# YakupTrkn1.net
KiCad netlist of a schematic drawn in Altium Designer
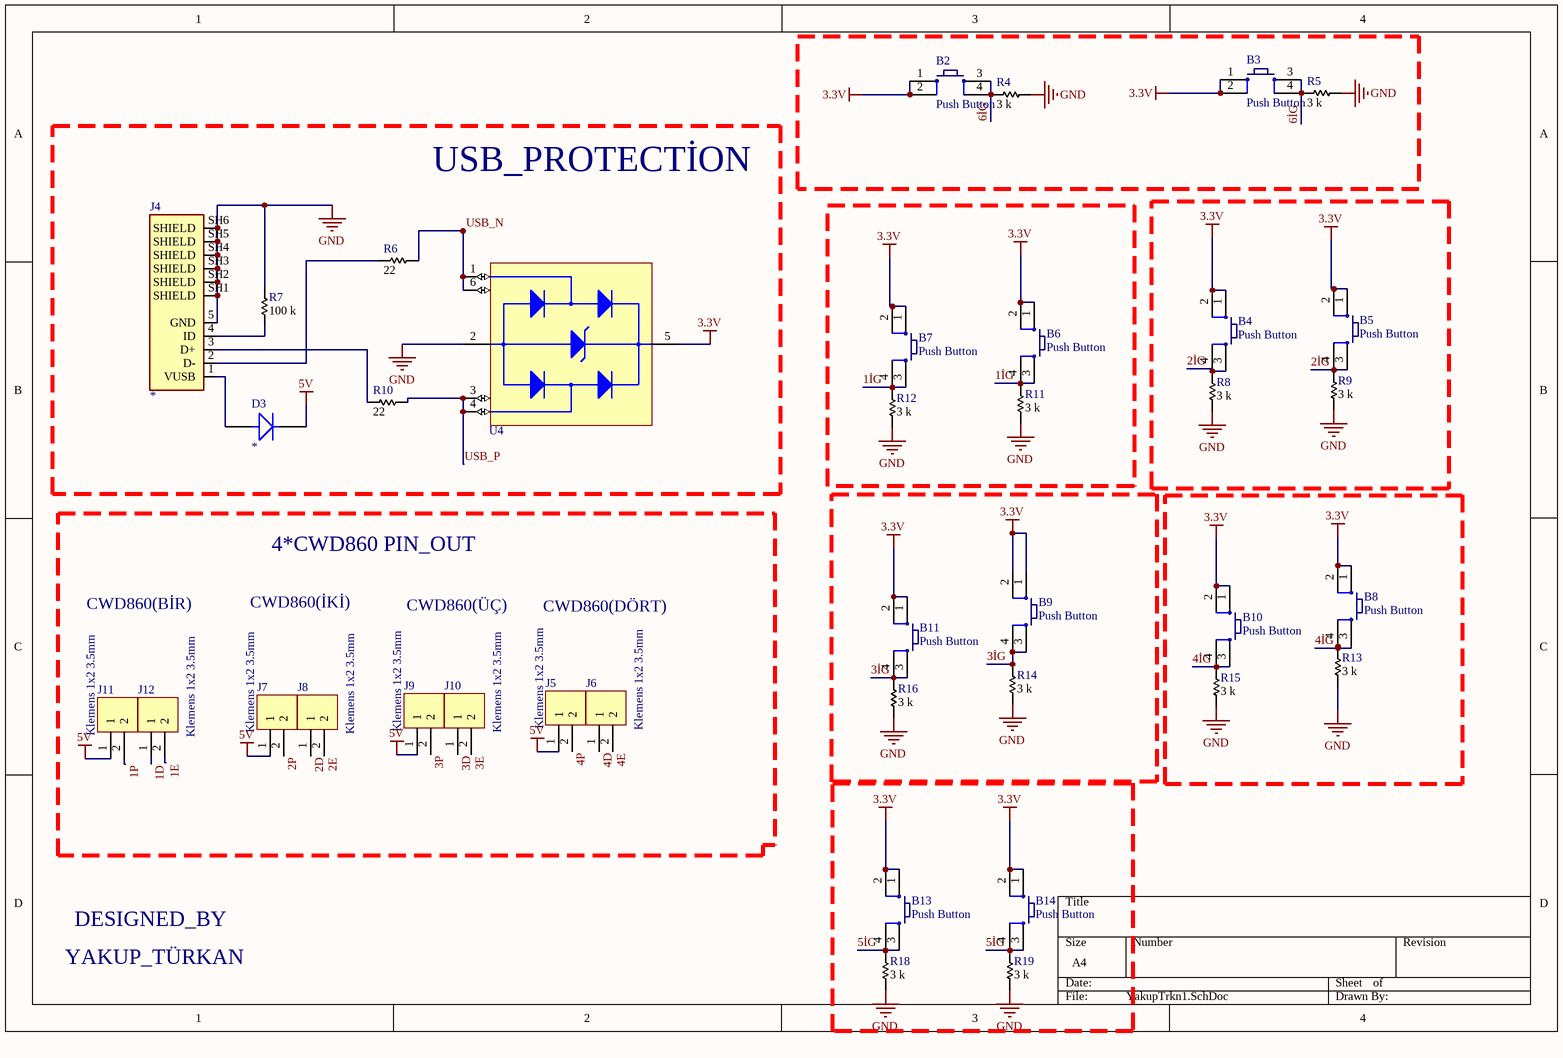
[diagram p0: YakupTrkn1.SchDoc]

(export (version "E")
  (design (tool "Eeschema 10.0.6"))
  (components
    (comp (ref "B2")
      (value "Push Button")
      (footprint "PUSB BUTTON-SMD")
      (description "Smd Push Button")
      (libsource (lib "YakupTrkn") (part "Push Button"))
    )
    (comp (ref "B3")
      (value "Push Button")
      (footprint "PUSB BUTTON-SMD")
      (description "Smd Push Button")
      (libsource (lib "YakupTrkn") (part "Push Button"))
    )
    (comp (ref "B4")
      (value "Push Button")
      (footprint "PUSB BUTTON-SMD")
      (description "Smd Push Button")
      (libsource (lib "YakupTrkn") (part "Push Button"))
    )
    (comp (ref "B5")
      (value "Push Button")
      (footprint "PUSB BUTTON-SMD")
      (description "Smd Push Button")
      (libsource (lib "YakupTrkn") (part "Push Button"))
    )
    (comp (ref "B6")
      (value "Push Button")
      (footprint "PUSB BUTTON-SMD")
      (description "Smd Push Button")
      (libsource (lib "YakupTrkn") (part "Push Button"))
    )
    (comp (ref "B7")
      (value "Push Button")
      (footprint "PUSB BUTTON-SMD")
      (description "Smd Push Button")
      (libsource (lib "YakupTrkn") (part "Push Button"))
    )
    (comp (ref "B8")
      (value "Push Button")
      (footprint "PUSB BUTTON-SMD")
      (description "Smd Push Button")
      (libsource (lib "YakupTrkn") (part "Push Button"))
    )
    (comp (ref "B9")
      (value "Push Button")
      (footprint "PUSB BUTTON-SMD")
      (description "Smd Push Button")
      (libsource (lib "YakupTrkn") (part "Push Button"))
    )
    (comp (ref "B10")
      (value "Push Button")
      (footprint "PUSB BUTTON-SMD")
      (description "Smd Push Button")
      (libsource (lib "YakupTrkn") (part "Push Button"))
    )
    (comp (ref "B11")
      (value "Push Button")
      (footprint "PUSB BUTTON-SMD")
      (description "Smd Push Button")
      (libsource (lib "YakupTrkn") (part "Push Button"))
    )
    (comp (ref "B13")
      (value "Push Button")
      (footprint "PUSB BUTTON-SMD")
      (description "Smd Push Button")
      (libsource (lib "YakupTrkn") (part "Push Button"))
    )
    (comp (ref "B14")
      (value "Push Button")
      (footprint "PUSB BUTTON-SMD")
      (description "Smd Push Button")
      (libsource (lib "YakupTrkn") (part "Push Button"))
    )
    (comp (ref "D3")
      (value "*")
      (footprint "MBRA210LT3G:DIOM5226X220N")
      (description "...employing the Schottky Barrier principle in a metal to silicon power rectifier.")
      (fields (field (name "MF") "{'manufacturer': u'ON Semiconductor'}") (field (name "MP") "MBRA210LT3G"))
      (libsource (lib "*") (part "MBRA210LT3G"))
    )
    (comp (ref "J4")
      (value "*")
      (footprint "10118192-0001LF:AMPHENOL_10118192-0001LF")
      (description "Single Port 5 Contact Horizontal Right Angle Shielded Micro B USB 2.0 Connector")
      (fields (field (name "MP") "10118192-0001LF") (field (name "MF") "{'manufacturer': u'FCI'}"))
      (libsource (lib "*") (part "10118192-0001LF"))
    )
    (comp (ref "J5")
      (value "Klemens 1x2 3.5mm")
      (footprint "Klemens 1x2 - 3.5mm")
      (libsource (lib "YakupTrkn") (part "Klemens 1x2 3.5mm"))
    )
    (comp (ref "J6")
      (value "Klemens 1x2 3.5mm")
      (footprint "Klemens 1x2 - 3.5mm")
      (libsource (lib "YakupTrkn") (part "Klemens 1x2 3.5mm"))
    )
    (comp (ref "J7")
      (value "Klemens 1x2 3.5mm")
      (footprint "Klemens 1x2 - 3.5mm")
      (libsource (lib "YakupTrkn") (part "Klemens 1x2 3.5mm"))
    )
    (comp (ref "J8")
      (value "Klemens 1x2 3.5mm")
      (footprint "Klemens 1x2 - 3.5mm")
      (libsource (lib "YakupTrkn") (part "Klemens 1x2 3.5mm"))
    )
    (comp (ref "J9")
      (value "Klemens 1x2 3.5mm")
      (footprint "Klemens 1x2 - 3.5mm")
      (libsource (lib "YakupTrkn") (part "Klemens 1x2 3.5mm"))
    )
    (comp (ref "J10")
      (value "Klemens 1x2 3.5mm")
      (footprint "Klemens 1x2 - 3.5mm")
      (libsource (lib "YakupTrkn") (part "Klemens 1x2 3.5mm"))
    )
    (comp (ref "J11")
      (value "Klemens 1x2 3.5mm")
      (footprint "Klemens 1x2 - 3.5mm")
      (libsource (lib "YakupTrkn") (part "Klemens 1x2 3.5mm"))
    )
    (comp (ref "J12")
      (value "Klemens 1x2 3.5mm")
      (footprint "Klemens 1x2 - 3.5mm")
      (libsource (lib "YakupTrkn") (part "Klemens 1x2 3.5mm"))
    )
    (comp (ref "R4")
      (value "0805S8F3001T5E")
      (footprint "ROYALOHM_RES_0805")
      (description "RES SMD 3K OHM 1% 1/8W 0805")
      (fields (field (name "RESISTANCE") "3 k"))
      (libsource (lib "YakupTrkn") (part "0805S8F3001T5E"))
    )
    (comp (ref "R5")
      (value "0805S8F3001T5E")
      (footprint "ROYALOHM_RES_0805")
      (description "RES SMD 3K OHM 1% 1/8W 0805")
      (fields (field (name "RESISTANCE") "3 k"))
      (libsource (lib "YakupTrkn") (part "0805S8F3001T5E"))
    )
    (comp (ref "R6")
      (value "0805W8J0220T5E")
      (footprint "ROYALOHM_RES_0805")
      (description "RES SMD 22 OHM 5% 1/8W 0805")
      (fields (field (name "RESISTANCE") "22"))
      (libsource (lib "YakupTrkn") (part "0805W8J0220T5E"))
    )
    (comp (ref "R7")
      (value "0603SAJ0104T5E")
      (footprint "ROYALOHM_RES_0603")
      (description "RES SMD 100K OHM 5% 1/10W 0603")
      (fields (field (name "RESISTANCE") "100 k"))
      (libsource (lib "YakupTrkn") (part "0603SAJ0104T5E"))
    )
    (comp (ref "R8")
      (value "0805S8F3001T5E")
      (footprint "ROYALOHM_RES_0805")
      (description "RES SMD 3K OHM 1% 1/8W 0805")
      (fields (field (name "RESISTANCE") "3 k"))
      (libsource (lib "YakupTrkn") (part "0805S8F3001T5E"))
    )
    (comp (ref "R9")
      (value "0805S8F3001T5E")
      (footprint "ROYALOHM_RES_0805")
      (description "RES SMD 3K OHM 1% 1/8W 0805")
      (fields (field (name "RESISTANCE") "3 k"))
      (libsource (lib "YakupTrkn") (part "0805S8F3001T5E"))
    )
    (comp (ref "R10")
      (value "0805W8J0220T5E")
      (footprint "ROYALOHM_RES_0805")
      (description "RES SMD 22 OHM 5% 1/8W 0805")
      (fields (field (name "RESISTANCE") "22"))
      (libsource (lib "YakupTrkn") (part "0805W8J0220T5E"))
    )
    (comp (ref "R11")
      (value "0805S8F3001T5E")
      (footprint "ROYALOHM_RES_0805")
      (description "RES SMD 3K OHM 1% 1/8W 0805")
      (fields (field (name "RESISTANCE") "3 k"))
      (libsource (lib "YakupTrkn") (part "0805S8F3001T5E"))
    )
    (comp (ref "R12")
      (value "0805S8F3001T5E")
      (footprint "ROYALOHM_RES_0805")
      (description "RES SMD 3K OHM 1% 1/8W 0805")
      (fields (field (name "RESISTANCE") "3 k"))
      (libsource (lib "YakupTrkn") (part "0805S8F3001T5E"))
    )
    (comp (ref "R13")
      (value "0805S8F3001T5E")
      (footprint "ROYALOHM_RES_0805")
      (description "RES SMD 3K OHM 1% 1/8W 0805")
      (fields (field (name "RESISTANCE") "3 k"))
      (libsource (lib "YakupTrkn") (part "0805S8F3001T5E"))
    )
    (comp (ref "R14")
      (value "0805S8F3001T5E")
      (footprint "ROYALOHM_RES_0805")
      (description "RES SMD 3K OHM 1% 1/8W 0805")
      (fields (field (name "RESISTANCE") "3 k"))
      (libsource (lib "YakupTrkn") (part "0805S8F3001T5E"))
    )
    (comp (ref "R15")
      (value "0805S8F3001T5E")
      (footprint "ROYALOHM_RES_0805")
      (description "RES SMD 3K OHM 1% 1/8W 0805")
      (fields (field (name "RESISTANCE") "3 k"))
      (libsource (lib "YakupTrkn") (part "0805S8F3001T5E"))
    )
    (comp (ref "R16")
      (value "0805S8F3001T5E")
      (footprint "ROYALOHM_RES_0805")
      (description "RES SMD 3K OHM 1% 1/8W 0805")
      (fields (field (name "RESISTANCE") "3 k"))
      (libsource (lib "YakupTrkn") (part "0805S8F3001T5E"))
    )
    (comp (ref "R18")
      (value "0805S8F3001T5E")
      (footprint "ROYALOHM_RES_0805")
      (description "RES SMD 3K OHM 1% 1/8W 0805")
      (fields (field (name "RESISTANCE") "3 k"))
      (libsource (lib "YakupTrkn") (part "0805S8F3001T5E"))
    )
    (comp (ref "R19")
      (value "0805S8F3001T5E")
      (footprint "ROYALOHM_RES_0805")
      (description "RES SMD 3K OHM 1% 1/8W 0805")
      (fields (field (name "RESISTANCE") "3 k"))
      (libsource (lib "YakupTrkn") (part "0805S8F3001T5E"))
    )
    (comp (ref "U4")
      (value "USBLC6-2SC6")
      (footprint "SOT23-6L")
      (description "TVS DIODE 5.25V 17V SOT23-6")
      (fields (field (name "MANUFACTURER") "STMicroelectronics") (field (name "DESIGNED BY") "BERK"))
      (libsource (lib "YakupTrkn") (part "USB PROTECTION"))
    )
  )
  (nets
    (net (code "1") (name "/1D") (class "Default")
      (node (ref "J12") (pin "1") (pinfunction "1_1") (pintype "passive"))
    )
    (net (code "2") (name "/1E") (class "Default")
      (node (ref "J12") (pin "2") (pinfunction "2_2") (pintype "passive"))
    )
    (net (code "3") (name "/1P") (class "Default")
      (node (ref "J11") (pin "2") (pinfunction "2_2") (pintype "passive"))
    )
    (net (code "4") (name "/1İG") (class "Default")
      (node (ref "B6") (pin "3") (pinfunction "3_3") (pintype "passive"))
      (node (ref "B6") (pin "4") (pinfunction "4_4") (pintype "passive"))
      (node (ref "B7") (pin "3") (pinfunction "3_3") (pintype "passive"))
      (node (ref "B7") (pin "4") (pinfunction "4_4") (pintype "passive"))
      (node (ref "R11") (pin "2") (pinfunction "2_2") (pintype "passive"))
      (node (ref "R12") (pin "2") (pinfunction "2_2") (pintype "passive"))
    )
    (net (code "5") (name "/2D") (class "Default")
      (node (ref "J8") (pin "1") (pinfunction "1_1") (pintype "passive"))
    )
    (net (code "6") (name "/2E") (class "Default")
      (node (ref "J8") (pin "2") (pinfunction "2_2") (pintype "passive"))
    )
    (net (code "7") (name "/2P") (class "Default")
      (node (ref "J7") (pin "2") (pinfunction "2_2") (pintype "passive"))
    )
    (net (code "8") (name "/2İG") (class "Default")
      (node (ref "B4") (pin "3") (pinfunction "3_3") (pintype "passive"))
      (node (ref "B4") (pin "4") (pinfunction "4_4") (pintype "passive"))
      (node (ref "B5") (pin "3") (pinfunction "3_3") (pintype "passive"))
      (node (ref "B5") (pin "4") (pinfunction "4_4") (pintype "passive"))
      (node (ref "R8") (pin "2") (pinfunction "2_2") (pintype "passive"))
      (node (ref "R9") (pin "2") (pinfunction "2_2") (pintype "passive"))
    )
    (net (code "9") (name "/3D") (class "Default")
      (node (ref "J10") (pin "1") (pinfunction "1_1") (pintype "passive"))
    )
    (net (code "10") (name "/3E") (class "Default")
      (node (ref "J10") (pin "2") (pinfunction "2_2") (pintype "passive"))
    )
    (net (code "11") (name "/3P") (class "Default")
      (node (ref "J9") (pin "2") (pinfunction "2_2") (pintype "passive"))
    )
    (net (code "12") (name "/3İG") (class "Default")
      (node (ref "B11") (pin "3") (pinfunction "3_3") (pintype "passive"))
      (node (ref "B11") (pin "4") (pinfunction "4_4") (pintype "passive"))
      (node (ref "B9") (pin "3") (pinfunction "3_3") (pintype "passive"))
      (node (ref "B9") (pin "4") (pinfunction "4_4") (pintype "passive"))
      (node (ref "R14") (pin "2") (pinfunction "2_2") (pintype "passive"))
      (node (ref "R16") (pin "2") (pinfunction "2_2") (pintype "passive"))
    )
    (net (code "13") (name "/4D") (class "Default")
      (node (ref "J6") (pin "1") (pinfunction "1_1") (pintype "passive"))
    )
    (net (code "14") (name "/4E") (class "Default")
      (node (ref "J6") (pin "2") (pinfunction "2_2") (pintype "passive"))
    )
    (net (code "15") (name "/4P") (class "Default")
      (node (ref "J5") (pin "2") (pinfunction "2_2") (pintype "passive"))
    )
    (net (code "16") (name "/4İG") (class "Default")
      (node (ref "B10") (pin "3") (pinfunction "3_3") (pintype "passive"))
      (node (ref "B10") (pin "4") (pinfunction "4_4") (pintype "passive"))
      (node (ref "B8") (pin "3") (pinfunction "3_3") (pintype "passive"))
      (node (ref "B8") (pin "4") (pinfunction "4_4") (pintype "passive"))
      (node (ref "R13") (pin "2") (pinfunction "2_2") (pintype "passive"))
      (node (ref "R15") (pin "2") (pinfunction "2_2") (pintype "passive"))
    )
    (net (code "17") (name "/5İG") (class "Default")
      (node (ref "B13") (pin "3") (pinfunction "3_3") (pintype "passive"))
      (node (ref "B13") (pin "4") (pinfunction "4_4") (pintype "passive"))
      (node (ref "B14") (pin "3") (pinfunction "3_3") (pintype "passive"))
      (node (ref "B14") (pin "4") (pinfunction "4_4") (pintype "passive"))
      (node (ref "R18") (pin "2") (pinfunction "2_2") (pintype "passive"))
      (node (ref "R19") (pin "2") (pinfunction "2_2") (pintype "passive"))
    )
    (net (code "18") (name "/6İG") (class "Default")
      (node (ref "B2") (pin "3") (pinfunction "3_3") (pintype "passive"))
      (node (ref "B2") (pin "4") (pinfunction "4_4") (pintype "passive"))
      (node (ref "B3") (pin "3") (pinfunction "3_3") (pintype "passive"))
      (node (ref "B3") (pin "4") (pinfunction "4_4") (pintype "passive"))
      (node (ref "R4") (pin "2") (pinfunction "2_2") (pintype "passive"))
      (node (ref "R5") (pin "2") (pinfunction "2_2") (pintype "passive"))
    )
    (net (code "19") (name "/USB_N") (class "Default")
      (node (ref "R6") (pin "2") (pinfunction "2_2") (pintype "passive"))
      (node (ref "U4") (pin "1") (pinfunction "I/O1_1") (pintype "bidirectional"))
      (node (ref "U4") (pin "6") (pinfunction "I/O1_6") (pintype "bidirectional"))
    )
    (net (code "20") (name "/USB_P") (class "Default")
      (node (ref "R10") (pin "2") (pinfunction "2_2") (pintype "passive"))
      (node (ref "U4") (pin "3") (pinfunction "I/O2_3") (pintype "bidirectional"))
      (node (ref "U4") (pin "4") (pinfunction "I/O2_4") (pintype "bidirectional"))
    )
    (net (code "21") (name "3.3V") (class "Default")
      (node (ref "B10") (pin "1") (pinfunction "1_1") (pintype "passive"))
      (node (ref "B10") (pin "2") (pinfunction "2_2") (pintype "passive"))
      (node (ref "B11") (pin "1") (pinfunction "1_1") (pintype "passive"))
      (node (ref "B11") (pin "2") (pinfunction "2_2") (pintype "passive"))
      (node (ref "B13") (pin "1") (pinfunction "1_1") (pintype "passive"))
      (node (ref "B13") (pin "2") (pinfunction "2_2") (pintype "passive"))
      (node (ref "B14") (pin "1") (pinfunction "1_1") (pintype "passive"))
      (node (ref "B14") (pin "2") (pinfunction "2_2") (pintype "passive"))
      (node (ref "B2") (pin "1") (pinfunction "1_1") (pintype "passive"))
      (node (ref "B2") (pin "2") (pinfunction "2_2") (pintype "passive"))
      (node (ref "B3") (pin "1") (pinfunction "1_1") (pintype "passive"))
      (node (ref "B3") (pin "2") (pinfunction "2_2") (pintype "passive"))
      (node (ref "B4") (pin "1") (pinfunction "1_1") (pintype "passive"))
      (node (ref "B4") (pin "2") (pinfunction "2_2") (pintype "passive"))
      (node (ref "B5") (pin "1") (pinfunction "1_1") (pintype "passive"))
      (node (ref "B5") (pin "2") (pinfunction "2_2") (pintype "passive"))
      (node (ref "B6") (pin "1") (pinfunction "1_1") (pintype "passive"))
      (node (ref "B6") (pin "2") (pinfunction "2_2") (pintype "passive"))
      (node (ref "B7") (pin "1") (pinfunction "1_1") (pintype "passive"))
      (node (ref "B7") (pin "2") (pinfunction "2_2") (pintype "passive"))
      (node (ref "B8") (pin "1") (pinfunction "1_1") (pintype "passive"))
      (node (ref "B8") (pin "2") (pinfunction "2_2") (pintype "passive"))
      (node (ref "B9") (pin "1") (pinfunction "1_1") (pintype "passive"))
      (node (ref "B9") (pin "2") (pinfunction "2_2") (pintype "passive"))
      (node (ref "U4") (pin "5") (pinfunction "VBUS_5") (pintype "power_in"))
    )
    (net (code "22") (name "5V") (class "Default")
      (node (ref "D3") (pin "1") (pinfunction "K_1") (pintype "passive"))
      (node (ref "J11") (pin "1") (pinfunction "1_1") (pintype "passive"))
      (node (ref "J5") (pin "1") (pinfunction "1_1") (pintype "passive"))
      (node (ref "J7") (pin "1") (pinfunction "1_1") (pintype "passive"))
      (node (ref "J9") (pin "1") (pinfunction "1_1") (pintype "passive"))
    )
    (net (code "23") (name "GND") (class "Default")
      (node (ref "J4") (pin "5") (pinfunction "GND_5") (pintype "passive"))
      (node (ref "J4") (pin "SH1") (pinfunction "SHIELD_SH1") (pintype "passive"))
      (node (ref "J4") (pin "SH2") (pinfunction "SHIELD_SH2") (pintype "passive"))
      (node (ref "J4") (pin "SH3") (pinfunction "SHIELD_SH3") (pintype "passive"))
      (node (ref "J4") (pin "SH4") (pinfunction "SHIELD_SH4") (pintype "passive"))
      (node (ref "J4") (pin "SH5") (pinfunction "SHIELD_SH5") (pintype "passive"))
      (node (ref "J4") (pin "SH6") (pinfunction "SHIELD_SH6") (pintype "passive"))
      (node (ref "R11") (pin "1") (pinfunction "1_1") (pintype "passive"))
      (node (ref "R12") (pin "1") (pinfunction "1_1") (pintype "passive"))
      (node (ref "R13") (pin "1") (pinfunction "1_1") (pintype "passive"))
      (node (ref "R14") (pin "1") (pinfunction "1_1") (pintype "passive"))
      (node (ref "R15") (pin "1") (pinfunction "1_1") (pintype "passive"))
      (node (ref "R16") (pin "1") (pinfunction "1_1") (pintype "passive"))
      (node (ref "R18") (pin "1") (pinfunction "1_1") (pintype "passive"))
      (node (ref "R19") (pin "1") (pinfunction "1_1") (pintype "passive"))
      (node (ref "R4") (pin "1") (pinfunction "1_1") (pintype "passive"))
      (node (ref "R5") (pin "1") (pinfunction "1_1") (pintype "passive"))
      (node (ref "R7") (pin "2") (pinfunction "2_2") (pintype "passive"))
      (node (ref "R8") (pin "1") (pinfunction "1_1") (pintype "passive"))
      (node (ref "R9") (pin "1") (pinfunction "1_1") (pintype "passive"))
      (node (ref "U4") (pin "2") (pinfunction "GND_2") (pintype "power_in"))
    )
    (net (code "24") (name "Net-(D3-A)") (class "Default")
      (node (ref "D3") (pin "2") (pinfunction "A_2") (pintype "passive"))
      (node (ref "J4") (pin "1") (pinfunction "VUSB_1") (pintype "passive"))
    )
    (net (code "25") (name "Net-(J4-D+)") (class "Default")
      (node (ref "J4") (pin "3") (pinfunction "D+_3") (pintype "passive"))
      (node (ref "R10") (pin "1") (pinfunction "1_1") (pintype "passive"))
    )
    (net (code "26") (name "Net-(J4-D-)") (class "Default")
      (node (ref "J4") (pin "2") (pinfunction "D-_2") (pintype "passive"))
      (node (ref "R6") (pin "1") (pinfunction "1_1") (pintype "passive"))
    )
    (net (code "27") (name "Net-(J4-ID)") (class "Default")
      (node (ref "J4") (pin "4") (pinfunction "ID_4") (pintype "passive"))
      (node (ref "R7") (pin "1") (pinfunction "1_1") (pintype "passive"))
    )
  )
)
